# B155AA.net
KiCad netlist of a schematic drawn in Altium Designer
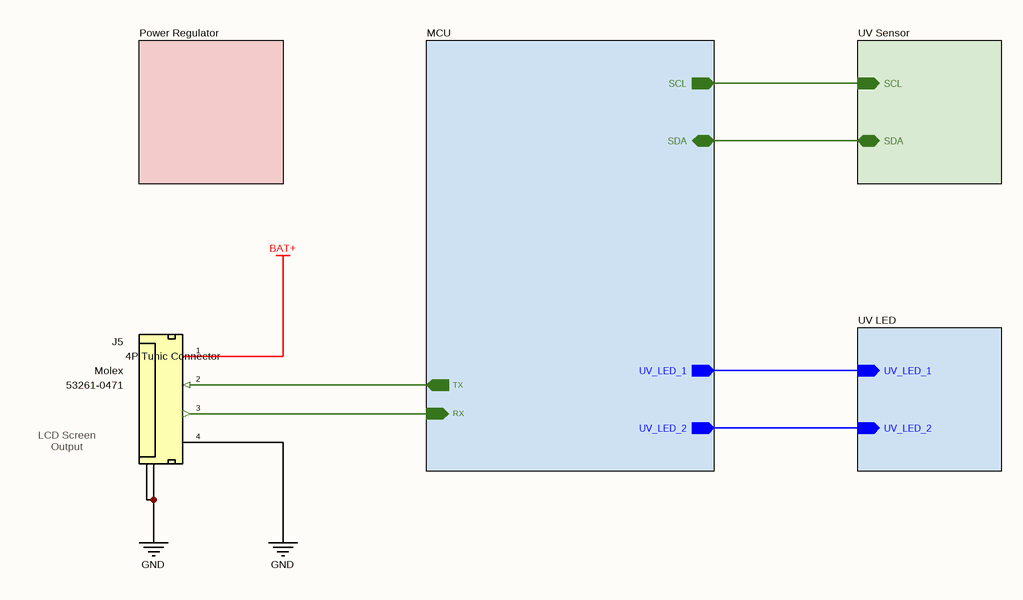
[diagram p0: B155AA.SchDoc]

(export (version "E")
  (design (tool "Eeschema 10.0.6"))
  (components
    (comp (ref "J5")
      (value "4P SMD Tunic Connector")
      (footprint "Connector_Tunic 4P")
      (description "Mini Tunic Connector with 4P")
      (fields
        (field (name "MANUFACTURER NAME") "Molex")
        (field (name "MANUFACTURER PART NUMBER") "53261-0471")
      )
      (libsource (lib "Akkoyun") (part "Connector - Mini Tunic 4P (1.25)"))
    )
  )
  (nets
    (net (code "1") (name "/RX") (class "Default")
      (node (ref "J5") (pin "3") (pinfunction "RX_3") (pintype "output"))
    )
    (net (code "4") (name "/TX") (class "Default")
      (node (ref "J5") (pin "2") (pinfunction "TX_2") (pintype "input"))
    )
    (net (code "7") (name "BAT+") (class "Default")
      (node (ref "J5") (pin "1") (pinfunction "BAT+_1") (pintype "passive"))
    )
    (net (code "8") (name "GND") (class "Default")
      (node (ref "J5") (pin "4") (pinfunction "BAT-_4") (pintype "passive"))
      (node (ref "J5") (pin "5") (pinfunction "GND_5") (pintype "passive"))
      (node (ref "J5") (pin "6") (pinfunction "GND_6") (pintype "passive"))
    )
  )
)
